# termocouple.net
KiCad netlist of a schematic drawn in EAGLE
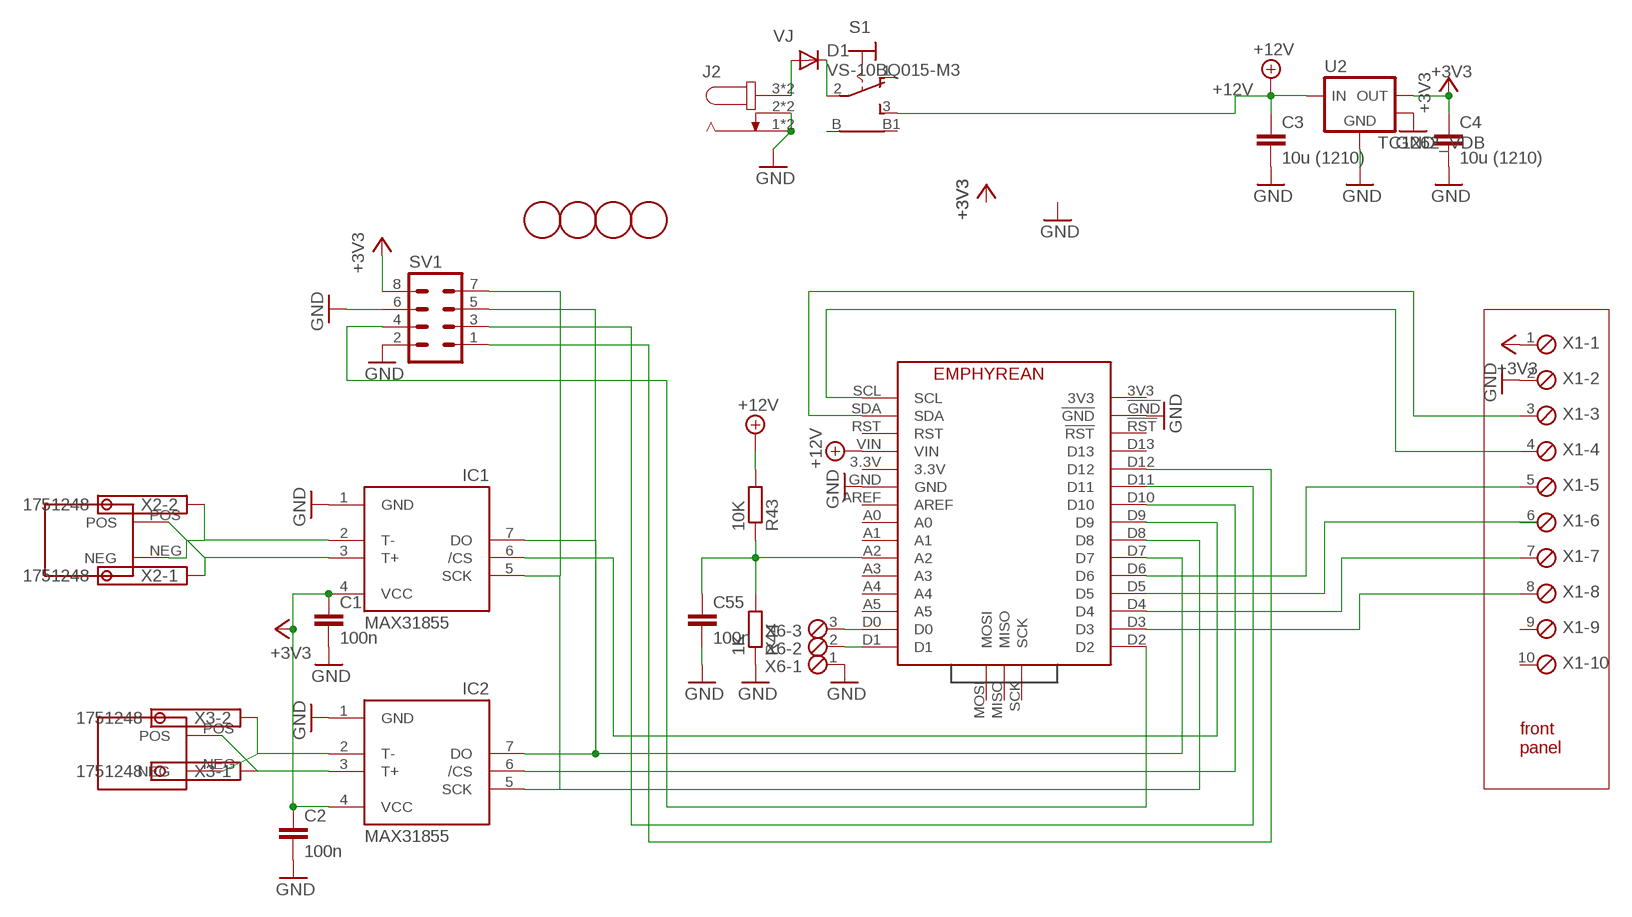
[diagram p0: schematic, sheet 1]

(export (version "E")
  (design (tool "Eeschema 10.0.6"))
  (components
    (comp (ref "C1")
      (value "100n")
      (footprint "eagle-import:C1206")
      (libsource (lib "eagle-import") (part "C-EUC1206"))
    )
    (comp (ref "C2")
      (value "100n")
      (footprint "eagle-import:C1206")
      (libsource (lib "eagle-import") (part "C-EUC1206"))
    )
    (comp (ref "C3")
      (value "10u (1210)")
      (footprint "eagle-import:C1210")
      (libsource (lib "eagle-import") (part "C-EUC1210"))
    )
    (comp (ref "C4")
      (value "10u (1210)")
      (footprint "eagle-import:C1210")
      (libsource (lib "eagle-import") (part "C-EUC1210"))
    )
    (comp (ref "C55")
      (value "100n")
      (footprint "eagle-import:C1206")
      (libsource (lib "eagle-import") (part "C-EUC1206"))
    )
    (comp (ref "D1")
      (value "VS-10BQ015-M3")
      (footprint "eagle-import:SMB")
      (libsource (lib "eagle-import") (part "DIODE-SMB"))
    )
    (comp (ref "IC1")
      (value "MAX31855")
      (footprint "eagle-import:SO08")
      (libsource (lib "eagle-import") (part "MAX6675"))
    )
    (comp (ref "IC2")
      (value "MAX31855")
      (footprint "eagle-import:SO08")
      (libsource (lib "eagle-import") (part "MAX6675"))
    )
    (comp (ref "J2")
      (value "JACK-PLUG")
      (footprint "eagle-import:SPC4078")
      (libsource (lib "eagle-import") (part "JACK-PLUG"))
    )
    (comp (ref "R43")
      (value "10K")
      (footprint "eagle-import:R1206")
      (libsource (lib "eagle-import") (part "R-EU_R1206"))
    )
    (comp (ref "R44")
      (value "1K")
      (footprint "eagle-import:R1206")
      (libsource (lib "eagle-import") (part "R-EU_R1206"))
    )
    (comp (ref "S1")
      (value "LPV-1")
      (footprint "eagle-import:LPV-1")
      (libsource (lib "eagle-import") (part "LPV-1"))
    )
    (comp (ref "SV1")
      (value "MA04-2")
      (footprint "eagle-import:MA04-2")
      (libsource (lib "eagle-import") (part "MA04-2"))
    )
    (comp (ref "U$1")
      (value "EPHYREAN")
      (footprint "eagle-import:EMPHYREAN")
      (libsource (lib "eagle-import") (part "EPHYREAN"))
    )
    (comp (ref "U$2")
      (value "THERMOCOUPLE")
      (footprint "eagle-import:THERMOCOUPLE")
      (libsource (lib "eagle-import") (part "THERMOCOUPLE"))
    )
    (comp (ref "U$3")
      (value "THERMOCOUPLE")
      (footprint "eagle-import:THERMOCOUPLE")
      (libsource (lib "eagle-import") (part "THERMOCOUPLE"))
    )
    (comp (ref "U$4")
      (value "FIDUCIAL")
      (footprint "eagle-import:FIDUCIAL_1MM")
      (libsource (lib "eagle-import") (part "FIDUCIAL"))
    )
    (comp (ref "U$5")
      (value "FIDUCIAL")
      (footprint "eagle-import:FIDUCIAL_1MM")
      (libsource (lib "eagle-import") (part "FIDUCIAL"))
    )
    (comp (ref "U$6")
      (value "FIDUCIAL")
      (footprint "eagle-import:FIDUCIAL_1MM")
      (libsource (lib "eagle-import") (part "FIDUCIAL"))
    )
    (comp (ref "U$7")
      (value "FIDUCIAL")
      (footprint "eagle-import:FIDUCIAL_1MM")
      (libsource (lib "eagle-import") (part "FIDUCIAL"))
    )
    (comp (ref "U2")
      (value "TC1262_VDB")
      (footprint "eagle-import:SOT-223-3")
      (libsource (lib "eagle-import") (part "TC1262_VDB"))
    )
    (comp (ref "X1")
      (value "MPT10")
      (footprint "eagle-import:10POL254")
      (libsource (lib "eagle-import") (part "MPT10"))
    )
    (comp (ref "X2")
      (value "1751248")
      (footprint "eagle-import:1751248")
      (libsource (lib "eagle-import") (part "1751248"))
    )
    (comp (ref "X3")
      (value "1751248")
      (footprint "eagle-import:1751248")
      (libsource (lib "eagle-import") (part "1751248"))
    )
    (comp (ref "X6")
      (value "MPT3")
      (footprint "eagle-import:3POL254")
      (libsource (lib "eagle-import") (part "MPT3"))
    )
  )
  (nets
    (net (code "1") (name "+3V3") (class "Default")
      (node (ref "C1") (pin "1") (pinfunction "1_1") (pintype "passive"))
      (node (ref "C2") (pin "1") (pinfunction "1_1") (pintype "passive"))
      (node (ref "C4") (pin "1") (pinfunction "1_1") (pintype "passive"))
      (node (ref "IC1") (pin "4") (pinfunction "VCC_4") (pintype "power_in"))
      (node (ref "IC2") (pin "4") (pinfunction "VCC_4") (pintype "power_in"))
      (node (ref "SV1") (pin "8") (pinfunction "8_8") (pintype "passive"))
      (node (ref "U2") (pin "3") (pinfunction "VOUT_3") (pintype "power_in"))
      (node (ref "X1") (pin "1") (pinfunction "1_1") (pintype "passive"))
    )
    (net (code "2") (name "+12V") (class "Default")
      (node (ref "C3") (pin "1") (pinfunction "1_1") (pintype "passive"))
      (node (ref "R43") (pin "2") (pinfunction "2_2") (pintype "passive"))
      (node (ref "S1") (pin "3") (pinfunction "S_3") (pintype "passive"))
      (node (ref "U$1") (pin "VIN") (pinfunction "VIN_VIN") (pintype "bidirectional"))
      (node (ref "U2") (pin "1") (pinfunction "VIN_1") (pintype "power_in"))
    )
    (net (code "3") (name "/VJ") (class "Default")
      (node (ref "D1") (pin "A") (pinfunction "A_A") (pintype "passive"))
      (node (ref "J2") (pin "3") (pinfunction "3_3") (pintype "passive"))
      (node (ref "J2") (pin "6") (pinfunction "3_6") (pintype "passive"))
    )
    (net (code "4") (name "GND") (class "Default")
      (node (ref "C1") (pin "2") (pinfunction "2_2") (pintype "passive"))
      (node (ref "C2") (pin "2") (pinfunction "2_2") (pintype "passive"))
      (node (ref "C3") (pin "2") (pinfunction "2_2") (pintype "passive"))
      (node (ref "C4") (pin "2") (pinfunction "2_2") (pintype "passive"))
      (node (ref "C55") (pin "2") (pinfunction "2_2") (pintype "passive"))
      (node (ref "IC1") (pin "1") (pinfunction "GND_1") (pintype "power_in"))
      (node (ref "IC2") (pin "1") (pinfunction "GND_1") (pintype "power_in"))
      (node (ref "J2") (pin "1") (pinfunction "1_1") (pintype "passive"))
      (node (ref "J2") (pin "2") (pinfunction "2_2") (pintype "passive"))
      (node (ref "J2") (pin "4") (pinfunction "1_4") (pintype "passive"))
      (node (ref "J2") (pin "5") (pinfunction "2_5") (pintype "passive"))
      (node (ref "R44") (pin "1") (pinfunction "1_1") (pintype "passive"))
      (node (ref "SV1") (pin "2") (pinfunction "2_2") (pintype "passive"))
      (node (ref "SV1") (pin "6") (pinfunction "6_6") (pintype "passive"))
      (node (ref "U$1") (pin "!GND") (pinfunction "~{GND}_!GND") (pintype "bidirectional"))
      (node (ref "U$1") (pin "GND") (pinfunction "GND_GND") (pintype "bidirectional"))
      (node (ref "U2") (pin "2") (pinfunction "GND_2") (pintype "power_in"))
      (node (ref "U2") (pin "4") (pinfunction "TAB_4") (pintype "power_in"))
      (node (ref "X1") (pin "2") (pinfunction "1_2") (pintype "passive"))
      (node (ref "X6") (pin "1") (pinfunction "1_1") (pintype "passive"))
    )
    (net (code "5") (name "Net-(C55-Pad1)") (class "Default")
      (node (ref "C55") (pin "1") (pinfunction "1_1") (pintype "passive"))
      (node (ref "R43") (pin "1") (pinfunction "1_1") (pintype "passive"))
      (node (ref "R44") (pin "2") (pinfunction "2_2") (pintype "passive"))
      (node (ref "U$1") (pin "A2") (pinfunction "A2_A2") (pintype "bidirectional"))
    )
    (net (code "6") (name "Net-(IC1-DO)") (class "Default")
      (node (ref "IC1") (pin "7") (pinfunction "DO_7") (pintype "output"))
      (node (ref "IC2") (pin "7") (pinfunction "DO_7") (pintype "output"))
      (node (ref "SV1") (pin "5") (pinfunction "5_5") (pintype "passive"))
      (node (ref "U$1") (pin "D7") (pinfunction "D7_D7") (pintype "bidirectional"))
    )
    (net (code "7") (name "Net-(IC1-SCK)") (class "Default")
      (node (ref "IC1") (pin "5") (pinfunction "SCK_5") (pintype "input"))
      (node (ref "IC2") (pin "5") (pinfunction "SCK_5") (pintype "input"))
      (node (ref "SV1") (pin "7") (pinfunction "7_7") (pintype "passive"))
      (node (ref "U$1") (pin "D8") (pinfunction "D8_D8") (pintype "bidirectional"))
    )
    (net (code "8") (name "Net-(IC1-T+)") (class "Default")
      (node (ref "IC1") (pin "3") (pinfunction "T+_3") (pintype "input"))
      (node (ref "U$3") (pin "POS") (pinfunction "POS_POS") (pintype "bidirectional"))
      (node (ref "X2") (pin "1") (pinfunction "K_1") (pintype "passive"))
    )
    (net (code "9") (name "Net-(IC1-T-)") (class "Default")
      (node (ref "IC1") (pin "2") (pinfunction "T-_2") (pintype "input"))
      (node (ref "U$3") (pin "NEG") (pinfunction "NEG_NEG") (pintype "bidirectional"))
      (node (ref "X2") (pin "2") (pinfunction "K_2") (pintype "passive"))
    )
    (net (code "10") (name "Net-(IC1-{slash}CS)") (class "Default")
      (node (ref "IC1") (pin "6") (pinfunction "/CS_6") (pintype "input"))
      (node (ref "U$1") (pin "D9") (pinfunction "D9_D9") (pintype "bidirectional"))
    )
    (net (code "11") (name "Net-(IC2-T+)") (class "Default")
      (node (ref "IC2") (pin "3") (pinfunction "T+_3") (pintype "input"))
      (node (ref "U$2") (pin "POS") (pinfunction "POS_POS") (pintype "bidirectional"))
      (node (ref "X3") (pin "1") (pinfunction "K_1") (pintype "passive"))
    )
    (net (code "12") (name "Net-(IC2-T-)") (class "Default")
      (node (ref "IC2") (pin "2") (pinfunction "T-_2") (pintype "input"))
      (node (ref "U$2") (pin "NEG") (pinfunction "NEG_NEG") (pintype "bidirectional"))
      (node (ref "X3") (pin "2") (pinfunction "K_2") (pintype "passive"))
    )
    (net (code "13") (name "Net-(IC2-{slash}CS)") (class "Default")
      (node (ref "IC2") (pin "6") (pinfunction "/CS_6") (pintype "input"))
      (node (ref "U$1") (pin "D10") (pinfunction "D10_D10") (pintype "bidirectional"))
    )
    (net (code "14") (name "Net-(S1-P)") (class "Default")
      (node (ref "D1") (pin "C") (pinfunction "C_C") (pintype "passive"))
      (node (ref "S1") (pin "2") (pinfunction "P_2") (pintype "passive"))
    )
    (net (code "15") (name "Net-(SV1-Pad1)") (class "Default")
      (node (ref "SV1") (pin "1") (pinfunction "1_1") (pintype "passive"))
      (node (ref "U$1") (pin "D12") (pinfunction "D12_D12") (pintype "bidirectional"))
    )
    (net (code "16") (name "Net-(SV1-Pad3)") (class "Default")
      (node (ref "SV1") (pin "3") (pinfunction "3_3") (pintype "passive"))
      (node (ref "U$1") (pin "D11") (pinfunction "D11_D11") (pintype "bidirectional"))
    )
    (net (code "17") (name "Net-(SV1-Pad4)") (class "Default")
      (node (ref "SV1") (pin "4") (pinfunction "4_4") (pintype "passive"))
      (node (ref "U$1") (pin "D2") (pinfunction "D2_D2") (pintype "bidirectional"))
    )
    (net (code "18") (name "Net-(X1D-1)") (class "Default")
      (node (ref "U$1") (pin "SDA") (pinfunction "SDA_SDA") (pintype "bidirectional"))
      (node (ref "X1") (pin "3") (pinfunction "1_3") (pintype "passive"))
    )
    (net (code "19") (name "Net-(X1E-1)") (class "Default")
      (node (ref "U$1") (pin "SCL") (pinfunction "SCL_SCL") (pintype "bidirectional"))
      (node (ref "X1") (pin "4") (pinfunction "1_4") (pintype "passive"))
    )
    (net (code "20") (name "Net-(X1F-1)") (class "Default")
      (node (ref "U$1") (pin "D6") (pinfunction "D6_D6") (pintype "bidirectional"))
      (node (ref "X1") (pin "5") (pinfunction "1_5") (pintype "passive"))
    )
    (net (code "21") (name "Net-(X1H-1)") (class "Default")
      (node (ref "U$1") (pin "D4") (pinfunction "D4_D4") (pintype "bidirectional"))
      (node (ref "X1") (pin "7") (pinfunction "1_7") (pintype "passive"))
    )
    (net (code "22") (name "Net-(X1I-1)") (class "Default")
      (node (ref "U$1") (pin "D3") (pinfunction "D3_D3") (pintype "bidirectional"))
      (node (ref "X1") (pin "8") (pinfunction "1_8") (pintype "passive"))
    )
    (net (code "23") (name "Net-(X6B-1)") (class "Default")
      (node (ref "U$1") (pin "D1") (pinfunction "D1_D1") (pintype "bidirectional"))
      (node (ref "X6") (pin "2") (pinfunction "1_2") (pintype "passive"))
    )
    (net (code "24") (name "Net-(X6C-1)") (class "Default")
      (node (ref "U$1") (pin "D0") (pinfunction "D0_D0") (pintype "bidirectional"))
      (node (ref "X6") (pin "3") (pinfunction "1_3") (pintype "passive"))
    )
    (net (code "25") (name "unconnected-(S1-O-Pad1)") (class "Default")
      (node (ref "S1") (pin "1") (pinfunction "O_1") (pintype "passive"))
    )
    (net (code "26") (name "unconnected-(S1-PadB)") (class "Default")
      (node (ref "S1") (pin "B") (pinfunction "B_B") (pintype "passive"))
    )
    (net (code "27") (name "unconnected-(S1-PadB1)") (class "Default")
      (node (ref "S1") (pin "B1") (pinfunction "B1_B1") (pintype "passive"))
    )
    (net (code "28") (name "unconnected-(U$1-Pad3.3V)") (class "Default")
      (node (ref "U$1") (pin "3.3V") (pinfunction "3.3V_3.3V") (pintype "bidirectional"))
    )
    (net (code "29") (name "unconnected-(U$1-Pad3V3)") (class "Default")
      (node (ref "U$1") (pin "3V3") (pinfunction "3V3_3V3") (pintype "bidirectional"))
    )
    (net (code "30") (name "unconnected-(U$1-PadA0)") (class "Default")
      (node (ref "U$1") (pin "A0") (pinfunction "A0_A0") (pintype "bidirectional"))
    )
    (net (code "31") (name "unconnected-(U$1-PadA1)") (class "Default")
      (node (ref "U$1") (pin "A1") (pinfunction "A1_A1") (pintype "bidirectional"))
    )
    (net (code "32") (name "unconnected-(U$1-PadA3)") (class "Default")
      (node (ref "U$1") (pin "A3") (pinfunction "A3_A3") (pintype "bidirectional"))
    )
    (net (code "33") (name "unconnected-(U$1-PadA4)") (class "Default")
      (node (ref "U$1") (pin "A4") (pinfunction "A4_A4") (pintype "bidirectional"))
    )
    (net (code "34") (name "unconnected-(U$1-PadA5)") (class "Default")
      (node (ref "U$1") (pin "A5") (pinfunction "A5_A5") (pintype "bidirectional"))
    )
    (net (code "35") (name "unconnected-(U$1-PadAREF)") (class "Default")
      (node (ref "U$1") (pin "AREF") (pinfunction "AREF_AREF") (pintype "bidirectional"))
    )
    (net (code "36") (name "unconnected-(U$1-PadD5)") (class "Default")
      (node (ref "U$1") (pin "D5") (pinfunction "D5_D5") (pintype "bidirectional"))
    )
    (net (code "37") (name "unconnected-(U$1-PadD13)") (class "Default")
      (node (ref "U$1") (pin "D13") (pinfunction "D13_D13") (pintype "bidirectional"))
    )
    (net (code "38") (name "unconnected-(U$1-PadMISO)") (class "Default")
      (node (ref "U$1") (pin "MISO") (pinfunction "MISO_MISO") (pintype "bidirectional"))
    )
    (net (code "39") (name "unconnected-(U$1-PadMOSI)") (class "Default")
      (node (ref "U$1") (pin "MOSI") (pinfunction "MOSI_MOSI") (pintype "bidirectional"))
    )
    (net (code "40") (name "unconnected-(U$1-PadRST)") (class "Default")
      (node (ref "U$1") (pin "RST") (pinfunction "RST_RST") (pintype "bidirectional"))
    )
    (net (code "41") (name "unconnected-(U$1-PadSCK)") (class "Default")
      (node (ref "U$1") (pin "SCK") (pinfunction "SCK_SCK") (pintype "bidirectional"))
    )
    (net (code "42") (name "unconnected-(U$1-~{RST}-Pad!RST)") (class "Default")
      (node (ref "U$1") (pin "!RST") (pinfunction "~{RST}_!RST") (pintype "bidirectional"))
    )
    (net (code "43") (name "unconnected-(X1B-1-Pad10)") (class "Default")
      (node (ref "X1") (pin "10") (pinfunction "1_10") (pintype "passive"))
    )
    (net (code "44") (name "unconnected-(X1G-1-Pad6)") (class "Default")
      (node (ref "X1") (pin "6") (pinfunction "1_6") (pintype "passive"))
    )
    (net (code "45") (name "unconnected-(X1J-1-Pad9)") (class "Default")
      (node (ref "X1") (pin "9") (pinfunction "1_9") (pintype "passive"))
    )
  )
)
